# Telemetry_Modul.net
KiCad netlist of a schematic drawn in Altium Designer
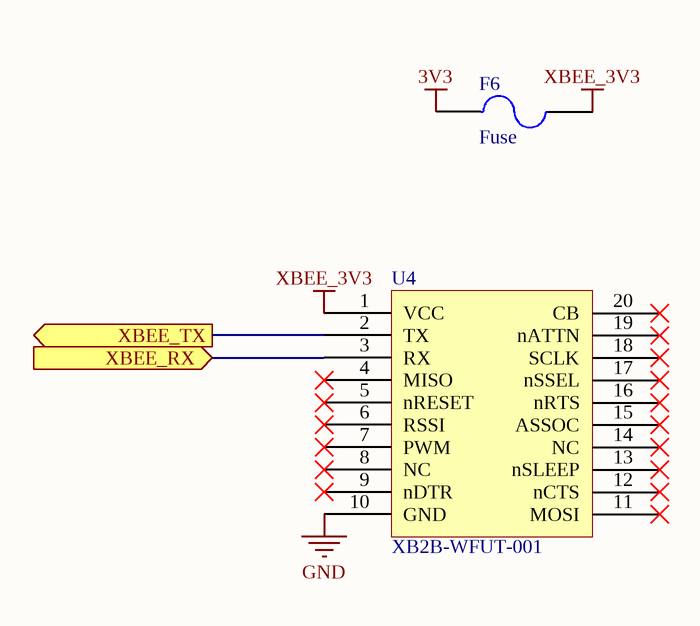
[diagram p0: Telemetry_Modul.SchDoc]

(export (version "E")
  (design (tool "Eeschema 10.0.6"))
  (components
    (comp (ref "F6")
      (value "Fuse")
      (footprint "F_0603")
      (fields (field (name "PART NUMBER") "MC06CF.500") (field (name "NI PART NUMBER") "766324-01"))
      (libsource (lib "Components") (part "Fuse"))
    )
    (comp (ref "U4")
      (value "XB2B-WFUT-001")
      (footprint "Components:XBee (WiFi)")
      (libsource (lib "Components") (part "XBee"))
    )
  )
  (nets
    (net (code "1") (name "/XBEE_RX") (class "Default")
      (node (ref "U4") (pin "3") (pinfunction "RX_3") (pintype "passive"))
    )
    (net (code "2") (name "/XBEE_TX") (class "Default")
      (node (ref "U4") (pin "2") (pinfunction "TX_2") (pintype "passive"))
    )
    (net (code "3") (name "3V3") (class "Default")
      (node (ref "F6") (pin "1") (pinfunction "1_1") (pintype "passive"))
    )
    (net (code "4") (name "GND") (class "Default")
      (node (ref "U4") (pin "10") (pinfunction "GND_10") (pintype "passive"))
    )
    (net (code "5") (name "XBEE_3V3") (class "Default")
      (node (ref "F6") (pin "2") (pinfunction "2_2") (pintype "passive"))
      (node (ref "U4") (pin "1") (pinfunction "VCC_1") (pintype "passive"))
    )
    (net (code "6") (name "unconnected-(U4-ASSOC-Pad15)") (class "Default")
      (node (ref "U4") (pin "15") (pinfunction "ASSOC_15") (pintype "passive+no_connect"))
    )
    (net (code "7") (name "unconnected-(U4-CB-Pad20)") (class "Default")
      (node (ref "U4") (pin "20") (pinfunction "CB_20") (pintype "passive+no_connect"))
    )
    (net (code "8") (name "unconnected-(U4-MISO-Pad4)") (class "Default")
      (node (ref "U4") (pin "4") (pinfunction "MISO_4") (pintype "passive+no_connect"))
    )
    (net (code "9") (name "unconnected-(U4-MOSI-Pad11)") (class "Default")
      (node (ref "U4") (pin "11") (pinfunction "MOSI_11") (pintype "passive+no_connect"))
    )
    (net (code "10") (name "unconnected-(U4-NC-Pad8)") (class "Default")
      (node (ref "U4") (pin "8") (pinfunction "NC_8") (pintype "passive+no_connect"))
    )
    (net (code "11") (name "unconnected-(U4-NC-Pad14)") (class "Default")
      (node (ref "U4") (pin "14") (pinfunction "NC_14") (pintype "passive+no_connect"))
    )
    (net (code "12") (name "unconnected-(U4-PWM-Pad7)") (class "Default")
      (node (ref "U4") (pin "7") (pinfunction "PWM_7") (pintype "passive+no_connect"))
    )
    (net (code "13") (name "unconnected-(U4-RSSI-Pad6)") (class "Default")
      (node (ref "U4") (pin "6") (pinfunction "RSSI_6") (pintype "passive+no_connect"))
    )
    (net (code "14") (name "unconnected-(U4-SCLK-Pad18)") (class "Default")
      (node (ref "U4") (pin "18") (pinfunction "SCLK_18") (pintype "passive+no_connect"))
    )
    (net (code "15") (name "unconnected-(U4-nATTN-Pad19)") (class "Default")
      (node (ref "U4") (pin "19") (pinfunction "nATTN_19") (pintype "passive+no_connect"))
    )
    (net (code "16") (name "unconnected-(U4-nCTS-Pad12)") (class "Default")
      (node (ref "U4") (pin "12") (pinfunction "nCTS_12") (pintype "passive+no_connect"))
    )
    (net (code "17") (name "unconnected-(U4-nDTR-Pad9)") (class "Default")
      (node (ref "U4") (pin "9") (pinfunction "nDTR_9") (pintype "passive+no_connect"))
    )
    (net (code "18") (name "unconnected-(U4-nRESET-Pad5)") (class "Default")
      (node (ref "U4") (pin "5") (pinfunction "nRESET_5") (pintype "passive+no_connect"))
    )
    (net (code "19") (name "unconnected-(U4-nRTS-Pad16)") (class "Default")
      (node (ref "U4") (pin "16") (pinfunction "nRTS_16") (pintype "passive+no_connect"))
    )
    (net (code "20") (name "unconnected-(U4-nSLEEP-Pad13)") (class "Default")
      (node (ref "U4") (pin "13") (pinfunction "nSLEEP_13") (pintype "passive+no_connect"))
    )
    (net (code "21") (name "unconnected-(U4-nSSEL-Pad17)") (class "Default")
      (node (ref "U4") (pin "17") (pinfunction "nSSEL_17") (pintype "passive+no_connect"))
    )
  )
)
